# dv_analog_interface_ch.net
KiCad netlist of a schematic drawn in Altium Designer
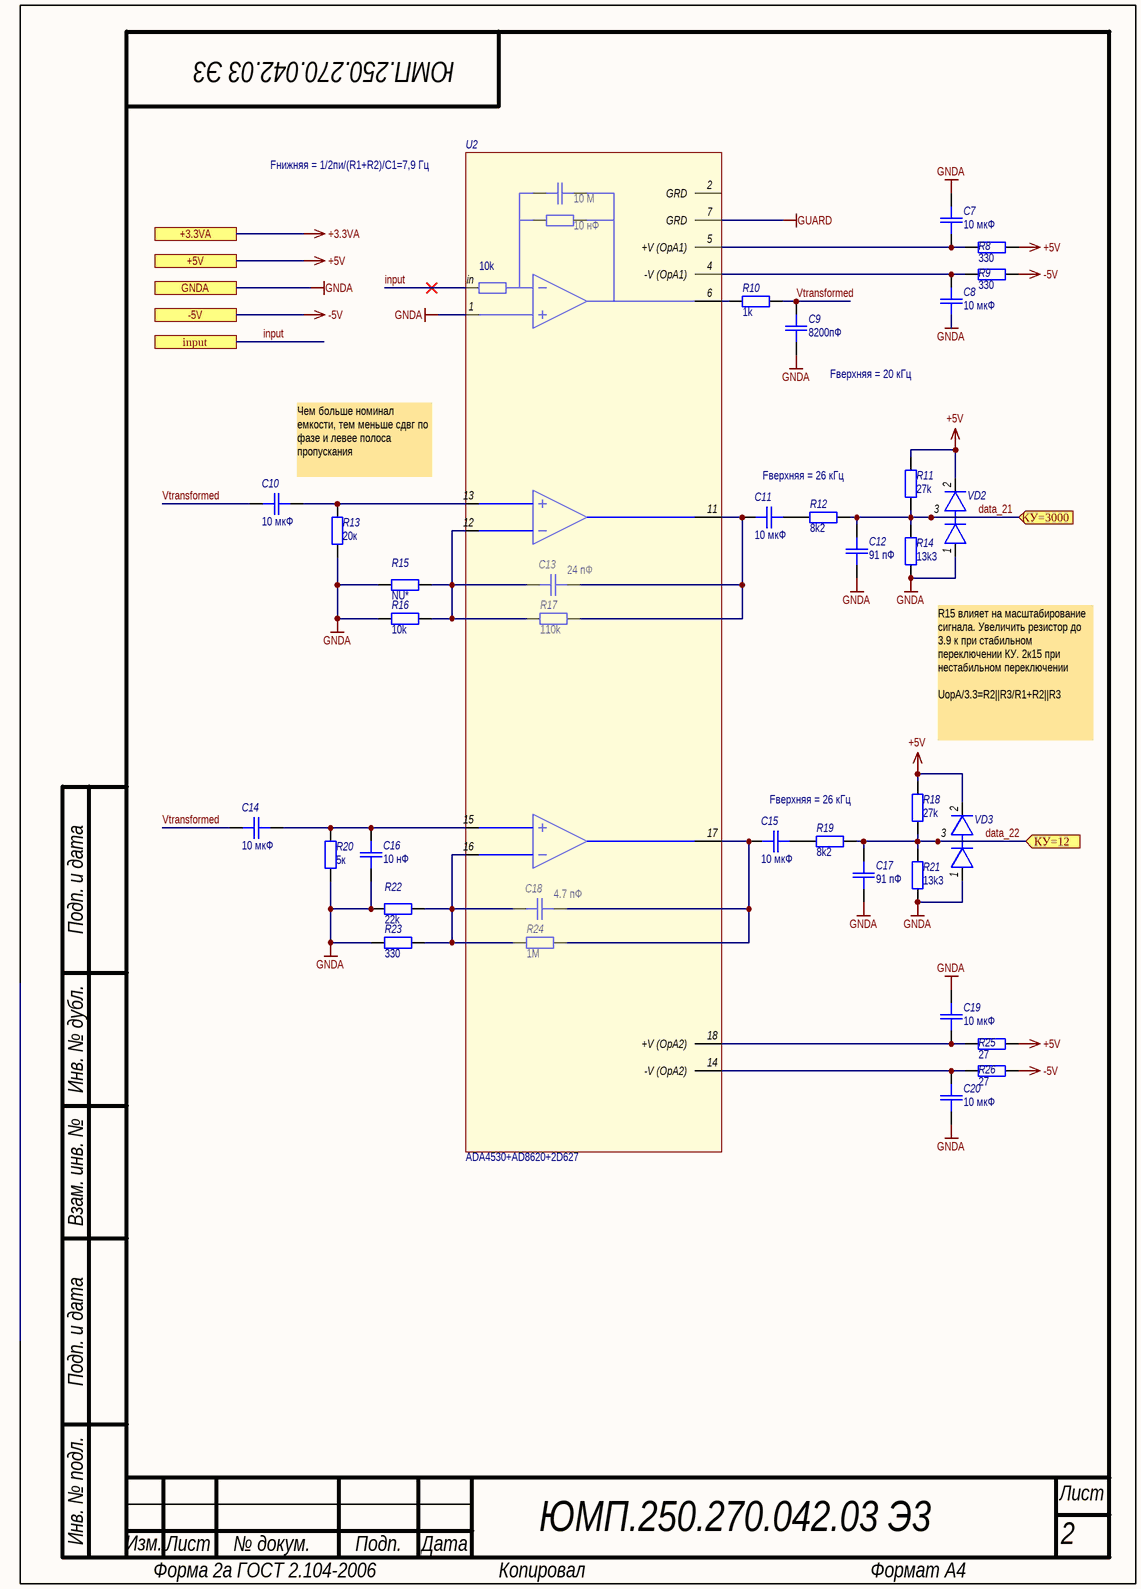
[diagram p0: dv_analog_interface_ch.SchDoc]

(export (version "E")
  (design (tool "Eeschema 10.0.6"))
  (components
    (comp (ref "C7")
      (value "10 мкФ")
      (footprint "SMD_C0805")
      (description "Capacitor")
      (fields (field (name "Comment") "K10-79"))
      (libsource (lib "Passive") (part "Capacitor"))
    )
    (comp (ref "C8")
      (value "10 мкФ")
      (footprint "SMD_C0805")
      (description "Capacitor")
      (fields (field (name "Comment") "K10-79"))
      (libsource (lib "Passive") (part "Capacitor"))
    )
    (comp (ref "C9")
      (value "8200пФ")
      (footprint "SMD_C0805")
      (description "Capacitor")
      (fields (field (name "Comment") "K10-79"))
      (libsource (lib "Passive") (part "Capacitor"))
    )
    (comp (ref "C10")
      (value "10 мкФ")
      (footprint "SMD_C0805")
      (description "Capacitor")
      (fields (field (name "Comment") "K10-79"))
      (libsource (lib "Passive") (part "Capacitor"))
    )
    (comp (ref "C11")
      (value "10 мкФ")
      (footprint "SMD_C0805")
      (description "Capacitor")
      (fields (field (name "Comment") "K10-79"))
      (libsource (lib "Passive") (part "Capacitor"))
    )
    (comp (ref "C12")
      (value "91 пФ")
      (footprint "SMD_C0805")
      (description "Capacitor")
      (fields (field (name "Comment") "K10-79"))
      (libsource (lib "Passive") (part "Capacitor"))
    )
    (comp (ref "C13")
      (value "24 пФ")
      (footprint "SMD_C0805")
      (description "Capacitor")
      (fields (field (name "Comment") "K10-79"))
      (libsource (lib "Passive") (part "Capacitor"))
    )
    (comp (ref "C14")
      (value "10 мкФ")
      (footprint "SMD_C0805")
      (description "Capacitor")
      (fields (field (name "Comment") "K10-79"))
      (libsource (lib "Passive") (part "Capacitor"))
    )
    (comp (ref "C15")
      (value "10 мкФ")
      (footprint "SMD_C0805")
      (description "Capacitor")
      (fields (field (name "Comment") "K10-79"))
      (libsource (lib "Passive") (part "Capacitor"))
    )
    (comp (ref "C16")
      (value "10 нФ")
      (footprint "SMD_C0805")
      (description "Capacitor")
      (fields (field (name "Comment") "K10-79"))
      (libsource (lib "Passive") (part "Capacitor"))
    )
    (comp (ref "C17")
      (value "91 пФ")
      (footprint "SMD_C0805")
      (description "Capacitor")
      (fields (field (name "Comment") "K10-79"))
      (libsource (lib "Passive") (part "Capacitor"))
    )
    (comp (ref "C18")
      (value "4.7 пФ")
      (footprint "SMD_C0805")
      (description "Capacitor")
      (fields (field (name "Comment") "K10-79"))
      (libsource (lib "Passive") (part "Capacitor"))
    )
    (comp (ref "C19")
      (value "10 мкФ")
      (footprint "SMD_C0805")
      (description "Capacitor")
      (fields (field (name "Comment") "K10-79"))
      (libsource (lib "Passive") (part "Capacitor"))
    )
    (comp (ref "C20")
      (value "10 мкФ")
      (footprint "SMD_C0805")
      (description "Capacitor")
      (fields (field (name "Comment") "K10-79"))
      (libsource (lib "Passive") (part "Capacitor"))
    )
    (comp (ref "R8")
      (value "330")
      (footprint "SMD_0805")
      (description "Resistor")
      (fields (field (name "Comment") "OSM R1-12"))
      (libsource (lib "") (part "Resistor_1"))
    )
    (comp (ref "R9")
      (value "330")
      (footprint "SMD_0805")
      (description "Resistor")
      (fields (field (name "Comment") "OSM R1-12"))
      (libsource (lib "") (part "Resistor_2"))
    )
    (comp (ref "R10")
      (value "1k")
      (footprint "SMD_0805")
      (description "Resistor")
      (fields (field (name "Comment") "OSM R1-12"))
      (libsource (lib "Passive") (part "Resistor"))
    )
    (comp (ref "R11")
      (value "27k")
      (footprint "SMD_0805")
      (description "Resistor")
      (fields (field (name "Comment") "OSM R1-12"))
      (libsource (lib "") (part "Resistor_1"))
    )
    (comp (ref "R12")
      (value "8k2")
      (footprint "SMD_0805")
      (description "Resistor")
      (fields (field (name "Comment") "OSM R1-12"))
      (libsource (lib "Passive") (part "Resistor"))
    )
    (comp (ref "R13")
      (value "20к")
      (footprint "SMD_0805")
      (description "Resistor")
      (fields (field (name "Comment") "OSM R1-12"))
      (libsource (lib "") (part "Resistor_1"))
    )
    (comp (ref "R14")
      (value "13k3")
      (footprint "SMD_0805")
      (description "Resistor")
      (fields (field (name "Comment") "OSM R1-12"))
      (libsource (lib "") (part "Resistor_1"))
    )
    (comp (ref "R15")
      (value "NU*")
      (footprint "SMD_0805")
      (description "Resistor")
      (fields (field (name "Comment") "OSM R1-12"))
      (libsource (lib "") (part "Resistor_2"))
    )
    (comp (ref "R16")
      (value "10k")
      (footprint "SMD_0805")
      (description "Resistor")
      (fields (field (name "Comment") "OSM R1-12"))
      (libsource (lib "") (part "Resistor_2"))
    )
    (comp (ref "R17")
      (value "110k")
      (footprint "SMD_0805")
      (description "Resistor")
      (fields (field (name "Comment") "OSM R1-12"))
      (libsource (lib "Passive") (part "Resistor"))
    )
    (comp (ref "R18")
      (value "27k")
      (footprint "SMD_0805")
      (description "Resistor")
      (fields (field (name "Comment") "OSM R1-12"))
      (libsource (lib "") (part "Resistor_1"))
    )
    (comp (ref "R19")
      (value "8k2")
      (footprint "SMD_0805")
      (description "Resistor")
      (fields (field (name "Comment") "OSM R1-12"))
      (libsource (lib "Passive") (part "Resistor"))
    )
    (comp (ref "R20")
      (value "5к")
      (footprint "SMD_0805")
      (description "Resistor")
      (fields (field (name "Comment") "OSM R1-12"))
      (libsource (lib "") (part "Resistor_1"))
    )
    (comp (ref "R21")
      (value "13k3")
      (footprint "SMD_0805")
      (description "Resistor")
      (fields (field (name "Comment") "OSM R1-12"))
      (libsource (lib "") (part "Resistor_1"))
    )
    (comp (ref "R22")
      (value "22k")
      (footprint "SMD_0805")
      (description "Resistor")
      (fields (field (name "Comment") "OSM R1-12"))
      (libsource (lib "") (part "Resistor_2"))
    )
    (comp (ref "R23")
      (value "330")
      (footprint "SMD_0805")
      (description "Resistor")
      (fields (field (name "Comment") "OSM R1-12"))
      (libsource (lib "") (part "Resistor_2"))
    )
    (comp (ref "R24")
      (value "1M")
      (footprint "SMD_0805")
      (description "Resistor")
      (fields (field (name "Comment") "OSM R1-12"))
      (libsource (lib "Passive") (part "Resistor"))
    )
    (comp (ref "R25")
      (value "27")
      (footprint "SMD_0805")
      (description "Resistor")
      (fields (field (name "Comment") "OSM R1-12"))
      (libsource (lib "") (part "Resistor_1"))
    )
    (comp (ref "R26")
      (value "27")
      (footprint "SMD_0805")
      (description "Resistor")
      (fields (field (name "Comment") "OSM R1-12"))
      (libsource (lib "") (part "Resistor_2"))
    )
    (comp (ref "U2")
      (value "ADA4530+AD8620+2D627")
      (footprint "401.16-3+soic.8:401.16-3+soic")
      (libsource (lib "Amplifier") (part "ADA4530+AD8620+2D627"))
    )
    (comp (ref "VD2")
      (value "BAT54SW")
      (footprint "SOT-323 (SC-70)")
      (description "Schottky diodes")
      (libsource (lib "BAT54SW") (part "BAT54SW"))
    )
    (comp (ref "VD3")
      (value "BAT54SW")
      (footprint "SOT-323 (SC-70)")
      (description "Schottky diodes")
      (libsource (lib "BAT54SW") (part "BAT54SW"))
    )
  )
  (nets
    (net (code "2") (name "+5V") (class "Default")
      (node (ref "R11") (pin "2") (pinfunction "2_2") (pintype "passive"))
      (node (ref "R18") (pin "2") (pinfunction "2_2") (pintype "passive"))
      (node (ref "R25") (pin "2") (pinfunction "2_2") (pintype "passive"))
      (node (ref "R8") (pin "2") (pinfunction "2_2") (pintype "passive"))
      (node (ref "VD2") (pin "2") (pinfunction "4_2") (pintype "passive"))
      (node (ref "VD3") (pin "2") (pinfunction "4_2") (pintype "passive"))
    )
    (net (code "3") (name "-5V") (class "Default")
      (node (ref "R26") (pin "1") (pinfunction "1_1") (pintype "passive"))
      (node (ref "R9") (pin "1") (pinfunction "1_1") (pintype "passive"))
    )
    (net (code "4") (name "/Vtransformed") (class "Default")
      (node (ref "C10") (pin "2") (pinfunction "2_2") (pintype "passive"))
      (node (ref "C14") (pin "2") (pinfunction "2_2") (pintype "passive"))
      (node (ref "C9") (pin "2") (pinfunction "2_2") (pintype "passive"))
      (node (ref "R10") (pin "2") (pinfunction "2_2") (pintype "passive"))
    )
    (net (code "5") (name "/data_21") (class "Default")
      (node (ref "C12") (pin "2") (pinfunction "2_2") (pintype "passive"))
      (node (ref "R11") (pin "1") (pinfunction "1_1") (pintype "passive"))
      (node (ref "R12") (pin "2") (pinfunction "2_2") (pintype "passive"))
      (node (ref "R14") (pin "2") (pinfunction "2_2") (pintype "passive"))
      (node (ref "VD2") (pin "3") (pinfunction "6_3") (pintype "passive"))
    )
    (net (code "6") (name "/data_22") (class "Default")
      (node (ref "C17") (pin "2") (pinfunction "2_2") (pintype "passive"))
      (node (ref "R18") (pin "1") (pinfunction "1_1") (pintype "passive"))
      (node (ref "R19") (pin "2") (pinfunction "2_2") (pintype "passive"))
      (node (ref "R21") (pin "2") (pinfunction "2_2") (pintype "passive"))
      (node (ref "VD3") (pin "3") (pinfunction "6_3") (pintype "passive"))
    )
    (net (code "7") (name "/input") (class "Default")
      (node (ref "U2") (pin "in") (pinfunction "1_in") (pintype "passive"))
    )
    (net (code "8") (name "GNDA") (class "Default")
      (node (ref "C12") (pin "1") (pinfunction "1_1") (pintype "passive"))
      (node (ref "C16") (pin "1") (pinfunction "1_1") (pintype "passive"))
      (node (ref "C17") (pin "1") (pinfunction "1_1") (pintype "passive"))
      (node (ref "C19") (pin "1") (pinfunction "1_1") (pintype "passive"))
      (node (ref "C20") (pin "2") (pinfunction "2_2") (pintype "passive"))
      (node (ref "C7") (pin "1") (pinfunction "1_1") (pintype "passive"))
      (node (ref "C8") (pin "2") (pinfunction "2_2") (pintype "passive"))
      (node (ref "C9") (pin "1") (pinfunction "1_1") (pintype "passive"))
      (node (ref "R13") (pin "1") (pinfunction "1_1") (pintype "passive"))
      (node (ref "R14") (pin "1") (pinfunction "1_1") (pintype "passive"))
      (node (ref "R15") (pin "2") (pinfunction "2_2") (pintype "passive"))
      (node (ref "R16") (pin "2") (pinfunction "2_2") (pintype "passive"))
      (node (ref "R20") (pin "1") (pinfunction "1_1") (pintype "passive"))
      (node (ref "R21") (pin "1") (pinfunction "1_1") (pintype "passive"))
      (node (ref "R22") (pin "2") (pinfunction "2_2") (pintype "passive"))
      (node (ref "R23") (pin "2") (pinfunction "2_2") (pintype "passive"))
      (node (ref "U2") (pin "1") (pinfunction "2_1") (pintype "passive"))
      (node (ref "VD2") (pin "1") (pinfunction "5_1") (pintype "passive"))
      (node (ref "VD3") (pin "1") (pinfunction "5_1") (pintype "passive"))
    )
    (net (code "9") (name "GUARD") (class "Default")
      (node (ref "U2") (pin "7") (pinfunction "GRD_7") (pintype "power_in"))
    )
    (net (code "10") (name "Net-(C11-Pad1)") (class "Default")
      (node (ref "C11") (pin "1") (pinfunction "1_1") (pintype "passive"))
      (node (ref "R12") (pin "1") (pinfunction "1_1") (pintype "passive"))
    )
    (net (code "11") (name "Net-(C11-Pad2)") (class "Default")
      (node (ref "C11") (pin "2") (pinfunction "2_2") (pintype "passive"))
      (node (ref "C13") (pin "1") (pinfunction "1_1") (pintype "passive"))
      (node (ref "R17") (pin "2") (pinfunction "2_2") (pintype "passive"))
      (node (ref "U2") (pin "11") (pintype "power_in"))
    )
    (net (code "12") (name "Net-(C13-Pad2)") (class "Default")
      (node (ref "C13") (pin "2") (pinfunction "2_2") (pintype "passive"))
      (node (ref "R15") (pin "1") (pinfunction "1_1") (pintype "passive"))
      (node (ref "R16") (pin "1") (pinfunction "1_1") (pintype "passive"))
      (node (ref "R17") (pin "1") (pinfunction "1_1") (pintype "passive"))
      (node (ref "U2") (pin "12") (pinfunction "4_12") (pintype "passive"))
    )
    (net (code "13") (name "Net-(C14-Pad1)") (class "Default")
      (node (ref "C14") (pin "1") (pinfunction "1_1") (pintype "passive"))
      (node (ref "C16") (pin "2") (pinfunction "2_2") (pintype "passive"))
      (node (ref "R20") (pin "2") (pinfunction "2_2") (pintype "passive"))
      (node (ref "U2") (pin "15") (pinfunction "4_15") (pintype "passive"))
    )
    (net (code "14") (name "Net-(C15-Pad1)") (class "Default")
      (node (ref "C15") (pin "1") (pinfunction "1_1") (pintype "passive"))
      (node (ref "R19") (pin "1") (pinfunction "1_1") (pintype "passive"))
    )
    (net (code "15") (name "Net-(C15-Pad2)") (class "Default")
      (node (ref "C15") (pin "2") (pinfunction "2_2") (pintype "passive"))
      (node (ref "C18") (pin "1") (pinfunction "1_1") (pintype "passive"))
      (node (ref "R24") (pin "2") (pinfunction "2_2") (pintype "passive"))
      (node (ref "U2") (pin "17") (pintype "power_in"))
    )
    (net (code "16") (name "Net-(R10-Pad1)") (class "Default")
      (node (ref "R10") (pin "1") (pinfunction "1_1") (pintype "passive"))
      (node (ref "U2") (pin "6") (pintype "power_in"))
    )
    (net (code "17") (name "Net-(U2-+V_(OpA1))") (class "Default")
      (node (ref "C7") (pin "2") (pinfunction "2_2") (pintype "passive"))
      (node (ref "R8") (pin "1") (pinfunction "1_1") (pintype "passive"))
      (node (ref "U2") (pin "5") (pinfunction "+V_(OpA1)_5") (pintype "power_in"))
    )
    (net (code "18") (name "Net-(U2-+V_(OpA2))") (class "Default")
      (node (ref "C19") (pin "2") (pinfunction "2_2") (pintype "passive"))
      (node (ref "R25") (pin "1") (pinfunction "1_1") (pintype "passive"))
      (node (ref "U2") (pin "18") (pinfunction "+V_(OpA2)_18") (pintype "power_in"))
    )
    (net (code "19") (name "Net-(U2--V_(OpA1))") (class "Default")
      (node (ref "C8") (pin "1") (pinfunction "1_1") (pintype "passive"))
      (node (ref "R9") (pin "2") (pinfunction "2_2") (pintype "passive"))
      (node (ref "U2") (pin "4") (pinfunction "-V_(OpA1)_4") (pintype "power_in"))
    )
    (net (code "20") (name "Net-(U2--V_(OpA2))") (class "Default")
      (node (ref "C20") (pin "1") (pinfunction "1_1") (pintype "passive"))
      (node (ref "R26") (pin "2") (pinfunction "2_2") (pintype "passive"))
      (node (ref "U2") (pin "14") (pinfunction "-V_(OpA2)_14") (pintype "power_in"))
    )
    (net (code "21") (name "Net-(U2-3)") (class "Default")
      (node (ref "C10") (pin "1") (pinfunction "1_1") (pintype "passive"))
      (node (ref "R13") (pin "2") (pinfunction "2_2") (pintype "passive"))
      (node (ref "U2") (pin "13") (pinfunction "3_13") (pintype "passive"))
    )
    (net (code "22") (name "Net-(U2-5)") (class "Default")
      (node (ref "C18") (pin "2") (pinfunction "2_2") (pintype "passive"))
      (node (ref "R22") (pin "1") (pinfunction "1_1") (pintype "passive"))
      (node (ref "R23") (pin "1") (pinfunction "1_1") (pintype "passive"))
      (node (ref "R24") (pin "1") (pinfunction "1_1") (pintype "passive"))
      (node (ref "U2") (pin "16") (pinfunction "5_16") (pintype "passive"))
    )
    (net (code "23") (name "unconnected-(U2-*-Padinput)") (class "Default")
      (node (ref "U2") (pin "input") (pinfunction "*_input") (pintype "passive"))
    )
    (net (code "24") (name "unconnected-(U2-2-Pad*)") (class "Default")
      (node (ref "U2") (pin "*") (pinfunction "2_*") (pintype "passive"))
    )
    (net (code "25") (name "unconnected-(U2-GRD-Pad2)") (class "Default")
      (node (ref "U2") (pin "2") (pinfunction "GRD_2") (pintype "power_in"))
    )
    (net (code "26") (name "unconnected-(U2-Pad1)") (class "Default")
      (node (ref "U2") (pin "1") (pinfunction "1_1") (pintype "passive"))
    )
    (net (code "27") (name "unconnected-(U2-Pad2)") (class "Default")
      (node (ref "U2") (pin "2") (pinfunction "2_2") (pintype "passive"))
    )
  )
)
